# WatsonV1.net
KiCad netlist of a schematic drawn in EAGLE
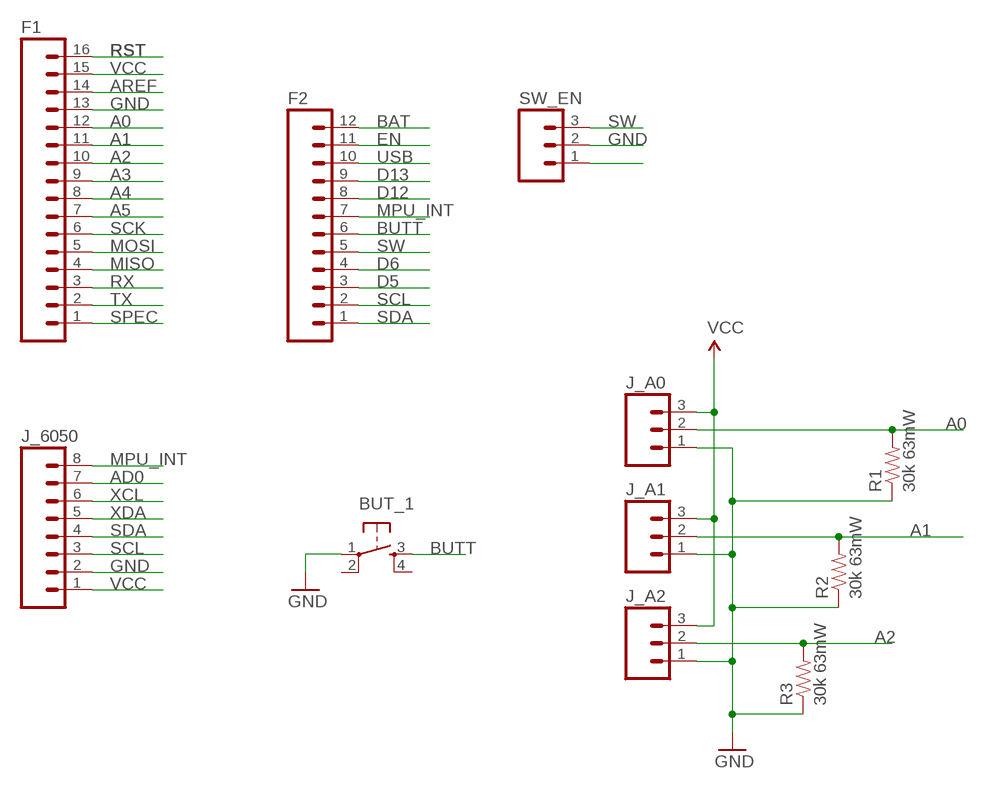
[diagram p0: schematic, sheet 1]

(export (version "E")
  (design (tool "Eeschema 10.0.6"))
  (components
    (comp (ref "BUT_1")
      (value "TAC_SWITCHPTH")
      (footprint "eagle-import:TACTILE-PTH")
      (libsource (lib "eagle-import") (part "TAC_SWITCHPTH"))
    )
    (comp (ref "F1")
      (value "M16PTH")
      (footprint "eagle-import:1X16")
      (libsource (lib "eagle-import") (part "M16PTH"))
    )
    (comp (ref "F2")
      (value "M12PTH")
      (footprint "eagle-import:1X12")
      (libsource (lib "eagle-import") (part "M12PTH"))
    )
    (comp (ref "J_6050")
      (value "M08")
      (footprint "eagle-import:1X08_ROUND")
      (libsource (lib "eagle-import") (part "M08"))
    )
    (comp (ref "J_A0")
      (value "M03JST-PTH-VERT")
      (footprint "eagle-import:JST-3-PTH-VERT")
      (libsource (lib "eagle-import") (part "M03JST-PTH-VERT"))
    )
    (comp (ref "J_A1")
      (value "M03JST-PTH-VERT")
      (footprint "eagle-import:JST-3-PTH-VERT")
      (libsource (lib "eagle-import") (part "M03JST-PTH-VERT"))
    )
    (comp (ref "J_A2")
      (value "M03JST-PTH-VERT")
      (footprint "eagle-import:JST-3-PTH-VERT")
      (libsource (lib "eagle-import") (part "M03JST-PTH-VERT"))
    )
    (comp (ref "R1")
      (value "30k 63mW")
      (footprint "eagle-import:1206")
      (libsource (lib "eagle-import") (part "RESISTOR1206"))
    )
    (comp (ref "R2")
      (value "30k 63mW")
      (footprint "eagle-import:1206")
      (libsource (lib "eagle-import") (part "RESISTOR1206"))
    )
    (comp (ref "R3")
      (value "30k 63mW")
      (footprint "eagle-import:1206")
      (libsource (lib "eagle-import") (part "RESISTOR1206"))
    )
    (comp (ref "SW_EN")
      (value "M03PTH")
      (footprint "eagle-import:1X03")
      (libsource (lib "eagle-import") (part "M03PTH"))
    )
  )
  (nets
    (net (code "1") (name "/A0") (class "Default")
      (node (ref "F1") (pin "12") (pinfunction "12_12") (pintype "passive"))
      (node (ref "J_A0") (pin "2") (pinfunction "2_2") (pintype "passive"))
      (node (ref "R1") (pin "2") (pinfunction "2_2") (pintype "passive"))
    )
    (net (code "2") (name "/A1") (class "Default")
      (node (ref "F1") (pin "11") (pinfunction "11_11") (pintype "passive"))
      (node (ref "J_A1") (pin "2") (pinfunction "2_2") (pintype "passive"))
      (node (ref "R2") (pin "2") (pinfunction "2_2") (pintype "passive"))
    )
    (net (code "3") (name "/A2") (class "Default")
      (node (ref "F1") (pin "10") (pinfunction "10_10") (pintype "passive"))
      (node (ref "J_A2") (pin "2") (pinfunction "2_2") (pintype "passive"))
      (node (ref "R3") (pin "2") (pinfunction "2_2") (pintype "passive"))
    )
    (net (code "4") (name "/A3") (class "Default")
      (node (ref "F1") (pin "9") (pinfunction "9_9") (pintype "passive"))
    )
    (net (code "5") (name "/A4") (class "Default")
      (node (ref "F1") (pin "8") (pinfunction "8_8") (pintype "passive"))
    )
    (net (code "6") (name "/A5") (class "Default")
      (node (ref "F1") (pin "7") (pinfunction "7_7") (pintype "passive"))
    )
    (net (code "7") (name "/AD0") (class "Default")
      (node (ref "J_6050") (pin "7") (pinfunction "7_7") (pintype "passive"))
    )
    (net (code "8") (name "/AREF") (class "Default")
      (node (ref "F1") (pin "14") (pinfunction "14_14") (pintype "passive"))
    )
    (net (code "9") (name "/BAT") (class "Default")
      (node (ref "F2") (pin "12") (pinfunction "12_12") (pintype "passive"))
    )
    (net (code "10") (name "/BUTT") (class "Default")
      (node (ref "BUT_1") (pin "3") (pinfunction "3_3") (pintype "passive"))
      (node (ref "F2") (pin "6") (pinfunction "6_6") (pintype "passive"))
    )
    (net (code "11") (name "/D5") (class "Default")
      (node (ref "F2") (pin "3") (pinfunction "3_3") (pintype "passive"))
    )
    (net (code "12") (name "/D6") (class "Default")
      (node (ref "F2") (pin "4") (pinfunction "4_4") (pintype "passive"))
    )
    (net (code "13") (name "/D12") (class "Default")
      (node (ref "F2") (pin "8") (pinfunction "8_8") (pintype "passive"))
    )
    (net (code "14") (name "/D13") (class "Default")
      (node (ref "F2") (pin "9") (pinfunction "9_9") (pintype "passive"))
    )
    (net (code "15") (name "/EN") (class "Default")
      (node (ref "F2") (pin "11") (pinfunction "11_11") (pintype "passive"))
    )
    (net (code "16") (name "/MISO") (class "Default")
      (node (ref "F1") (pin "4") (pinfunction "4_4") (pintype "passive"))
    )
    (net (code "17") (name "/MOSI") (class "Default")
      (node (ref "F1") (pin "5") (pinfunction "5_5") (pintype "passive"))
    )
    (net (code "18") (name "/MPU_INT") (class "Default")
      (node (ref "F2") (pin "7") (pinfunction "7_7") (pintype "passive"))
      (node (ref "J_6050") (pin "8") (pinfunction "8_8") (pintype "passive"))
    )
    (net (code "19") (name "/RST") (class "Default")
      (node (ref "F1") (pin "16") (pinfunction "16_16") (pintype "passive"))
    )
    (net (code "20") (name "/RX") (class "Default")
      (node (ref "F1") (pin "3") (pinfunction "3_3") (pintype "passive"))
    )
    (net (code "21") (name "/SCK") (class "Default")
      (node (ref "F1") (pin "6") (pinfunction "6_6") (pintype "passive"))
    )
    (net (code "22") (name "/SCL") (class "Default")
      (node (ref "F2") (pin "2") (pinfunction "2_2") (pintype "passive"))
      (node (ref "J_6050") (pin "3") (pinfunction "3_3") (pintype "passive"))
    )
    (net (code "23") (name "/SDA") (class "Default")
      (node (ref "F2") (pin "1") (pinfunction "1_1") (pintype "passive"))
      (node (ref "J_6050") (pin "4") (pinfunction "4_4") (pintype "passive"))
    )
    (net (code "24") (name "/SPEC") (class "Default")
      (node (ref "F1") (pin "1") (pinfunction "1_1") (pintype "passive"))
    )
    (net (code "25") (name "/SW") (class "Default")
      (node (ref "F2") (pin "5") (pinfunction "5_5") (pintype "passive"))
      (node (ref "SW_EN") (pin "3") (pinfunction "3_3") (pintype "passive"))
    )
    (net (code "26") (name "/TX") (class "Default")
      (node (ref "F1") (pin "2") (pinfunction "2_2") (pintype "passive"))
    )
    (net (code "27") (name "/USB") (class "Default")
      (node (ref "F2") (pin "10") (pinfunction "10_10") (pintype "passive"))
    )
    (net (code "28") (name "/XCL") (class "Default")
      (node (ref "J_6050") (pin "6") (pinfunction "6_6") (pintype "passive"))
    )
    (net (code "29") (name "/XDA") (class "Default")
      (node (ref "J_6050") (pin "5") (pinfunction "5_5") (pintype "passive"))
    )
    (net (code "30") (name "GND") (class "Default")
      (node (ref "BUT_1") (pin "1") (pinfunction "1_1") (pintype "passive"))
      (node (ref "F1") (pin "13") (pinfunction "13_13") (pintype "passive"))
      (node (ref "J_6050") (pin "2") (pinfunction "2_2") (pintype "passive"))
      (node (ref "J_A0") (pin "1") (pinfunction "1_1") (pintype "passive"))
      (node (ref "J_A1") (pin "1") (pinfunction "1_1") (pintype "passive"))
      (node (ref "J_A2") (pin "1") (pinfunction "1_1") (pintype "passive"))
      (node (ref "R1") (pin "1") (pinfunction "1_1") (pintype "passive"))
      (node (ref "R2") (pin "1") (pinfunction "1_1") (pintype "passive"))
      (node (ref "R3") (pin "1") (pinfunction "1_1") (pintype "passive"))
      (node (ref "SW_EN") (pin "2") (pinfunction "2_2") (pintype "passive"))
    )
    (net (code "31") (name "VCC") (class "Default")
      (node (ref "F1") (pin "15") (pinfunction "15_15") (pintype "passive"))
      (node (ref "J_6050") (pin "1") (pinfunction "1_1") (pintype "passive"))
      (node (ref "J_A0") (pin "3") (pinfunction "3_3") (pintype "passive"))
      (node (ref "J_A1") (pin "3") (pinfunction "3_3") (pintype "passive"))
      (node (ref "J_A2") (pin "3") (pinfunction "3_3") (pintype "passive"))
    )
    (net (code "32") (name "unconnected-(BUT_1-Pad2)") (class "Default")
      (node (ref "BUT_1") (pin "2") (pinfunction "2_2") (pintype "passive"))
    )
    (net (code "33") (name "unconnected-(BUT_1-Pad4)") (class "Default")
      (node (ref "BUT_1") (pin "4") (pinfunction "4_4") (pintype "passive"))
    )
    (net (code "34") (name "unconnected-(SW_EN-Pad1)") (class "Default")
      (node (ref "SW_EN") (pin "1") (pinfunction "1_1") (pintype "passive"))
    )
  )
)
